# irs-v5.net
KiCad netlist of a schematic drawn in EAGLE
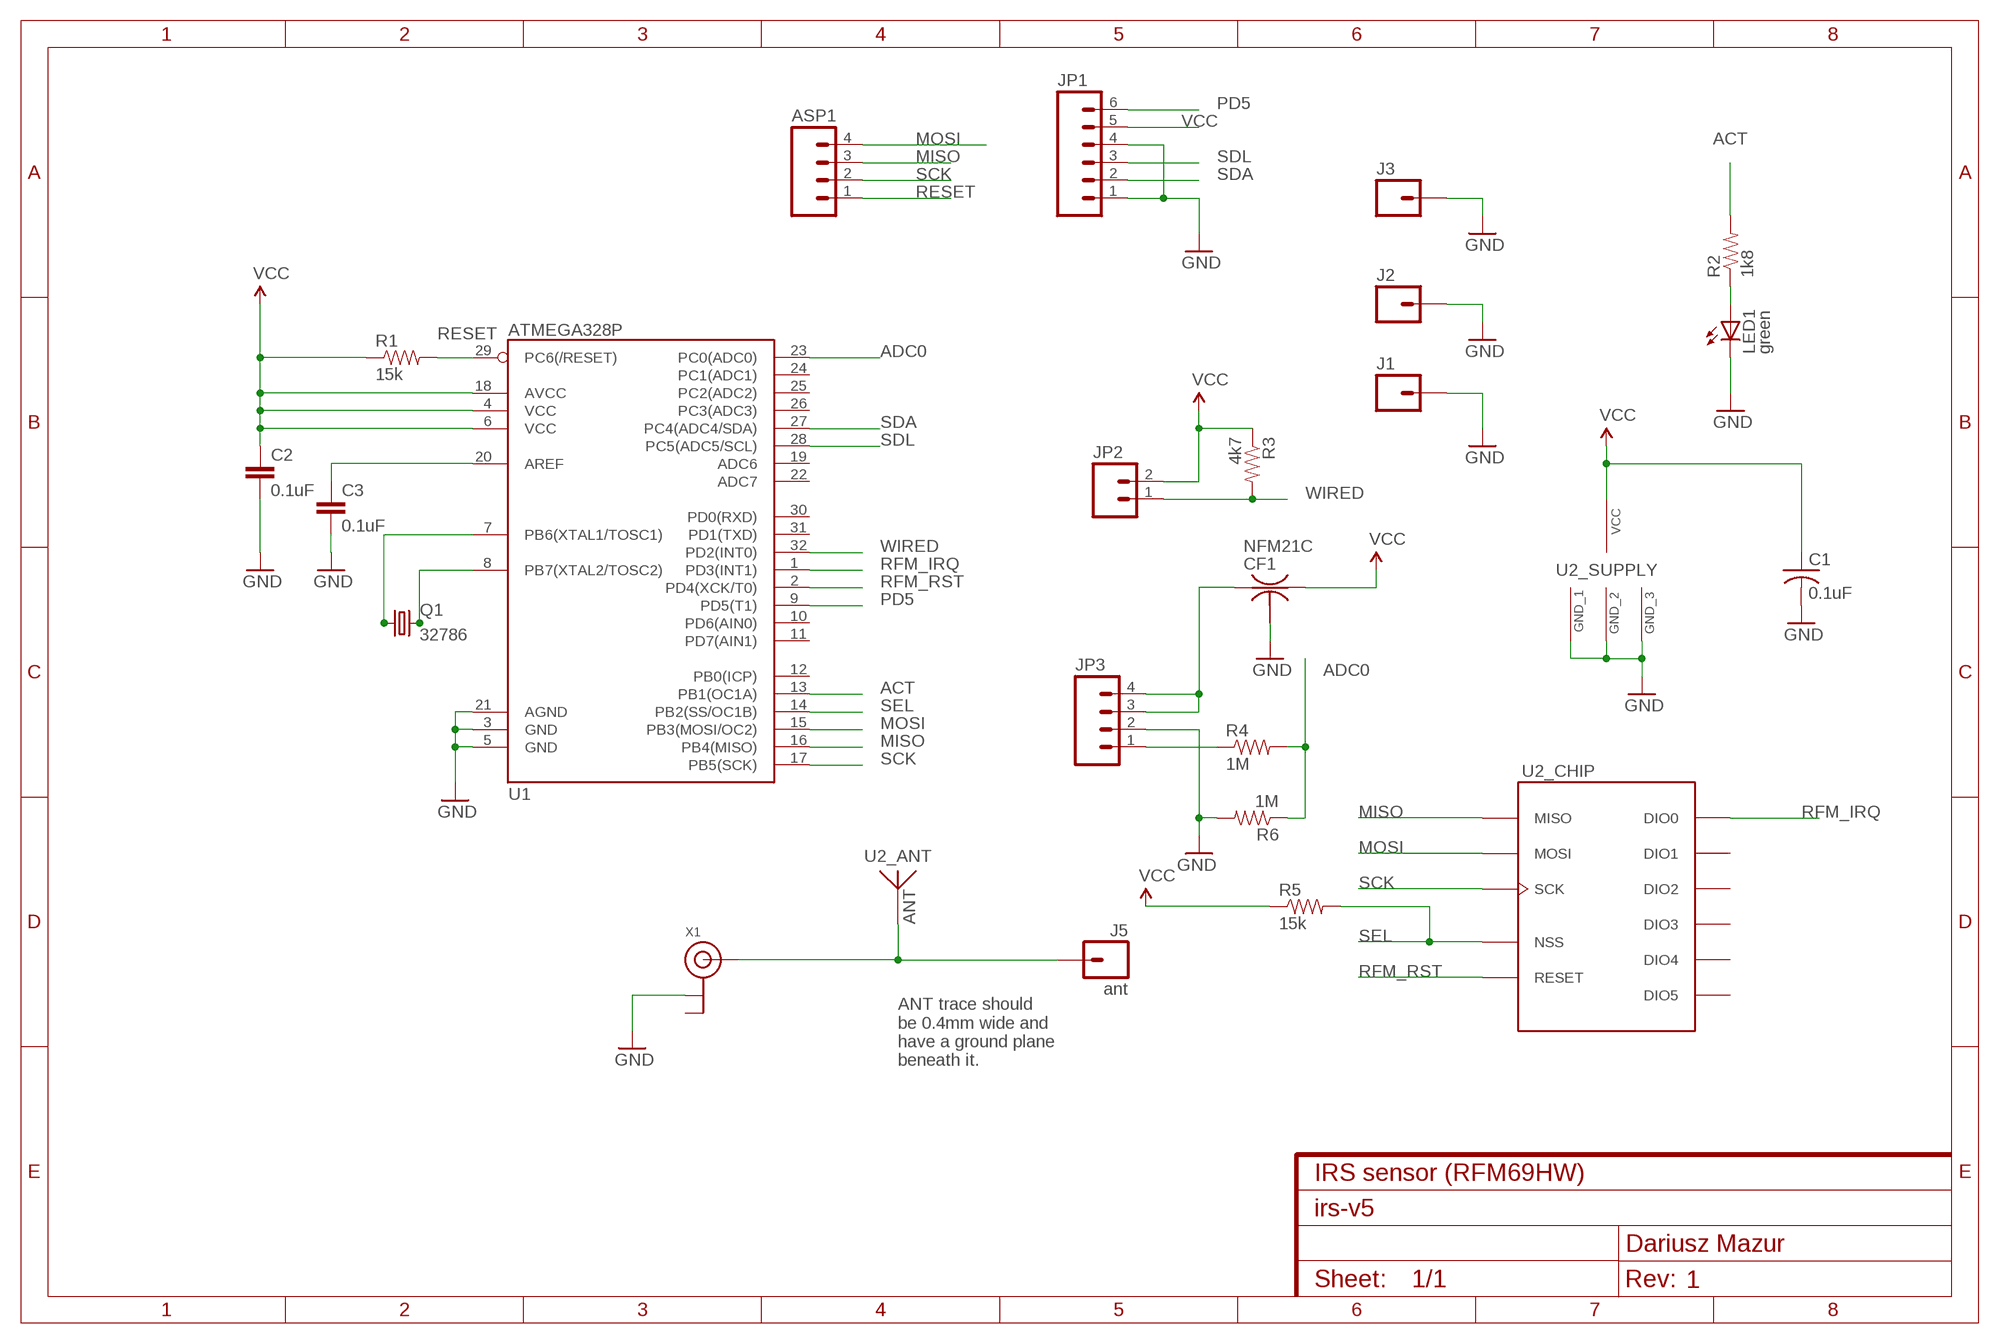
[diagram p0: schematic, sheet 1]

(export (version "E")
  (design (tool "Eeschema 10.0.6"))
  (components
    (comp (ref "ASP1")
      (value "M04NO_SILK_ALL_ROUND")
      (footprint "eagle-import:1X04_NO_SILK_ALL_ROUND")
      (libsource (lib "eagle-import") (part "M04NO_SILK_ALL_ROUND"))
    )
    (comp (ref "C1")
      (value "0.1uF")
      (footprint "eagle-import:C0603")
      (libsource (lib "eagle-import") (part "C-USC0603"))
    )
    (comp (ref "C2")
      (value "0.1uF")
      (footprint "eagle-import:0603-CAP")
      (libsource (lib "eagle-import") (part "0.1UF-25V(+80/-20%)(0603)"))
    )
    (comp (ref "C3")
      (value "0.1uF")
      (footprint "eagle-import:0603-CAP")
      (libsource (lib "eagle-import") (part "0.1UF-25V(+80/-20%)(0603)"))
    )
    (comp (ref "CF1")
      (value "NFM21C")
      (footprint "eagle-import:NFM21C")
      (fields (field (name "MPN") "NFM21CC102R1H3D"))
      (libsource (lib "eagle-import") (part "NFM21C"))
    )
    (comp (ref "J1")
      (value "M01PTH_NO_SILK_YES_STOP")
      (footprint "eagle-import:1X01_NO_SILK")
      (libsource (lib "eagle-import") (part "M01PTH_NO_SILK_YES_STOP"))
    )
    (comp (ref "J2")
      (value "M01PTH_NO_SILK_YES_STOP")
      (footprint "eagle-import:1X01_NO_SILK")
      (libsource (lib "eagle-import") (part "M01PTH_NO_SILK_YES_STOP"))
    )
    (comp (ref "J3")
      (value "M01PTH_NO_SILK_YES_STOP")
      (footprint "eagle-import:1X01_NO_SILK")
      (libsource (lib "eagle-import") (part "M01PTH_NO_SILK_YES_STOP"))
    )
    (comp (ref "J5")
      (value "ant")
      (footprint "eagle-import:1X01_NO_SILK")
      (libsource (lib "eagle-import") (part "M01PTH_NO_SILK_YES_STOP"))
    )
    (comp (ref "JP1")
      (value "M06NO_SILK_FEMALE_PTH")
      (footprint "eagle-import:1X06_NO_SILK")
      (libsource (lib "eagle-import") (part "M06NO_SILK_FEMALE_PTH"))
    )
    (comp (ref "JP2")
      (value "M021X02_NO_SILK")
      (footprint "eagle-import:1X02_NO_SILK")
      (libsource (lib "eagle-import") (part "M021X02_NO_SILK"))
    )
    (comp (ref "JP3")
      (value "M04NO_SILK_ALL_ROUND")
      (footprint "eagle-import:1X04_NO_SILK_ALL_ROUND")
      (libsource (lib "eagle-import") (part "M04NO_SILK_ALL_ROUND"))
    )
    (comp (ref "LED1")
      (value "green")
      (footprint "eagle-import:LED-0603")
      (libsource (lib "eagle-import") (part "LED0603"))
    )
    (comp (ref "Q1")
      (value "32786")
      (footprint "eagle-import:MC-306")
      (fields (field (name "MPN") "MC-306 60.0KHZ  100PPM ,12.5PF"))
      (libsource (lib "eagle-import") (part "MC-306"))
    )
    (comp (ref "R1")
      (value "15k")
      (footprint "eagle-import:0603-RES")
      (libsource (lib "eagle-import") (part "RESISTOR0603-RES"))
    )
    (comp (ref "R2")
      (value "1k8")
      (footprint "eagle-import:0603-RES")
      (libsource (lib "eagle-import") (part "RESISTOR0603-RES"))
    )
    (comp (ref "R3")
      (value "4k7")
      (footprint "eagle-import:0603-RES")
      (libsource (lib "eagle-import") (part "RESISTOR0603-RES"))
    )
    (comp (ref "R4")
      (value "1M")
      (footprint "eagle-import:0603-RES")
      (libsource (lib "eagle-import") (part "RESISTOR0603-RES"))
    )
    (comp (ref "R5")
      (value "15k")
      (footprint "eagle-import:0603-RES")
      (libsource (lib "eagle-import") (part "RESISTOR0603-RES"))
    )
    (comp (ref "R6")
      (value "1M")
      (footprint "eagle-import:0603-RES")
      (libsource (lib "eagle-import") (part "RESISTOR0603-RES"))
    )
    (comp (ref "U1")
      (value "ATMEGA328P")
      (footprint "eagle-import:TQFP32-08")
      (libsource (lib "eagle-import") (part "ATMEGA328_SMT"))
    )
    (comp (ref "U2")
      (value "RFM69HCW-S2")
      (footprint "eagle-import:HOPE-RF-16")
      (libsource (lib "eagle-import") (part "RFM69HCW-S2"))
    )
    (comp (ref "X1")
      (value "ANTENNA_U.FL")
      (footprint "eagle-import:U.FL")
      (libsource (lib "eagle-import") (part "ANTENNA_U.FL"))
    )
  )
  (nets
    (net (code "1") (name "/ACT") (class "Default")
      (node (ref "R2") (pin "2") (pinfunction "2_2") (pintype "passive"))
      (node (ref "U1") (pin "13") (pinfunction "PB1(OC1A)_13") (pintype "bidirectional"))
    )
    (net (code "2") (name "/ADC0") (class "Default")
      (node (ref "R4") (pin "2") (pinfunction "2_2") (pintype "passive"))
      (node (ref "R6") (pin "1") (pinfunction "1_1") (pintype "passive"))
      (node (ref "U1") (pin "23") (pinfunction "PC0(ADC0)_23") (pintype "bidirectional"))
    )
    (net (code "3") (name "/MISO") (class "Default")
      (node (ref "ASP1") (pin "3") (pinfunction "3_3") (pintype "passive"))
      (node (ref "U1") (pin "16") (pinfunction "PB4(MISO)_16") (pintype "bidirectional"))
      (node (ref "U2") (pin "MISO") (pinfunction "MISO_MISO") (pintype "input"))
    )
    (net (code "4") (name "/MOSI") (class "Default")
      (node (ref "ASP1") (pin "4") (pinfunction "4_4") (pintype "passive"))
      (node (ref "U1") (pin "15") (pinfunction "PB3(MOSI/OC2)_15") (pintype "bidirectional"))
      (node (ref "U2") (pin "MOSI") (pinfunction "MOSI_MOSI") (pintype "output"))
    )
    (net (code "5") (name "/PD5") (class "Default")
      (node (ref "JP1") (pin "6") (pinfunction "6_6") (pintype "passive"))
      (node (ref "U1") (pin "9") (pinfunction "PD5(T1)_9") (pintype "bidirectional"))
    )
    (net (code "6") (name "/RESET") (class "Default")
      (node (ref "ASP1") (pin "1") (pinfunction "1_1") (pintype "passive"))
      (node (ref "R1") (pin "2") (pinfunction "2_2") (pintype "passive"))
      (node (ref "U1") (pin "29") (pinfunction "PC6(/RESET)_29") (pintype "bidirectional"))
    )
    (net (code "7") (name "/RFM_IRQ") (class "Default")
      (node (ref "U1") (pin "1") (pinfunction "PD3(INT1)_1") (pintype "bidirectional"))
      (node (ref "U2") (pin "DIO0") (pinfunction "DIO0_DIO0") (pintype "bidirectional"))
    )
    (net (code "8") (name "/RFM_RST") (class "Default")
      (node (ref "U1") (pin "2") (pinfunction "PD4(XCK/T0)_2") (pintype "bidirectional"))
      (node (ref "U2") (pin "RESET") (pinfunction "RESET_RESET") (pintype "bidirectional"))
    )
    (net (code "9") (name "/SCK") (class "Default")
      (node (ref "ASP1") (pin "2") (pinfunction "2_2") (pintype "passive"))
      (node (ref "U1") (pin "17") (pinfunction "PB5(SCK)_17") (pintype "bidirectional"))
      (node (ref "U2") (pin "SCK") (pinfunction "SCK_SCK") (pintype "input"))
    )
    (net (code "10") (name "/SDA") (class "Default")
      (node (ref "JP1") (pin "2") (pinfunction "2_2") (pintype "passive"))
      (node (ref "U1") (pin "27") (pinfunction "PC4(ADC4/SDA)_27") (pintype "bidirectional"))
    )
    (net (code "11") (name "/SDL") (class "Default")
      (node (ref "JP1") (pin "3") (pinfunction "3_3") (pintype "passive"))
      (node (ref "U1") (pin "28") (pinfunction "PC5(ADC5/SCL)_28") (pintype "bidirectional"))
    )
    (net (code "12") (name "/SEL") (class "Default")
      (node (ref "R5") (pin "2") (pinfunction "2_2") (pintype "passive"))
      (node (ref "U1") (pin "14") (pinfunction "PB2(SS/OC1B)_14") (pintype "bidirectional"))
      (node (ref "U2") (pin "NSS") (pinfunction "NSS_NSS") (pintype "input"))
    )
    (net (code "13") (name "/WIRED") (class "Default")
      (node (ref "JP2") (pin "1") (pinfunction "1_1") (pintype "passive"))
      (node (ref "R3") (pin "2") (pinfunction "2_2") (pintype "passive"))
      (node (ref "U1") (pin "32") (pinfunction "PD2(INT0)_32") (pintype "bidirectional"))
    )
    (net (code "14") (name "GND") (class "Default")
      (node (ref "C1") (pin "2") (pinfunction "2_2") (pintype "passive"))
      (node (ref "C2") (pin "2") (pinfunction "2_2") (pintype "passive"))
      (node (ref "C3") (pin "2") (pinfunction "2_2") (pintype "passive"))
      (node (ref "CF1") (pin "2@1") (pinfunction "2_2@1") (pintype "passive"))
      (node (ref "J1") (pin "1") (pinfunction "1_1") (pintype "passive"))
      (node (ref "J2") (pin "1") (pinfunction "1_1") (pintype "passive"))
      (node (ref "J3") (pin "1") (pinfunction "1_1") (pintype "passive"))
      (node (ref "JP1") (pin "1") (pinfunction "1_1") (pintype "passive"))
      (node (ref "JP1") (pin "4") (pinfunction "4_4") (pintype "passive"))
      (node (ref "JP3") (pin "2") (pinfunction "2_2") (pintype "passive"))
      (node (ref "LED1") (pin "C") (pinfunction "C_C") (pintype "passive"))
      (node (ref "R6") (pin "2") (pinfunction "2_2") (pintype "passive"))
      (node (ref "U1") (pin "21") (pinfunction "AGND_21") (pintype "bidirectional"))
      (node (ref "U1") (pin "3") (pinfunction "GND_3") (pintype "bidirectional"))
      (node (ref "U1") (pin "5") (pinfunction "GND_5") (pintype "bidirectional"))
      (node (ref "U2") (pin "GND1") (pinfunction "GND_1_GND1") (pintype "power_in"))
      (node (ref "U2") (pin "GND2") (pinfunction "GND_2_GND2") (pintype "power_in"))
      (node (ref "U2") (pin "GND3") (pinfunction "GND_3_GND3") (pintype "power_in"))
      (node (ref "X1") (pin "1") (pinfunction "GND_1") (pintype "passive"))
    )
    (net (code "15") (name "Net-(CF1-Pad1)") (class "Default")
      (node (ref "CF1") (pin "1") (pinfunction "1_1") (pintype "passive"))
      (node (ref "JP3") (pin "3") (pinfunction "3_3") (pintype "passive"))
      (node (ref "JP3") (pin "4") (pinfunction "4_4") (pintype "passive"))
    )
    (net (code "16") (name "Net-(JP3-Pad1)") (class "Default")
      (node (ref "JP3") (pin "1") (pinfunction "1_1") (pintype "passive"))
      (node (ref "R4") (pin "1") (pinfunction "1_1") (pintype "passive"))
    )
    (net (code "17") (name "Net-(LED1-PadA)") (class "Default")
      (node (ref "LED1") (pin "A") (pinfunction "A_A") (pintype "passive"))
      (node (ref "R2") (pin "1") (pinfunction "1_1") (pintype "passive"))
    )
    (net (code "18") (name "Net-(Q1-2)") (class "Default")
      (node (ref "Q1") (pin "4") (pinfunction "2_4") (pintype "passive"))
      (node (ref "U1") (pin "8") (pinfunction "PB7(XTAL2/TOSC2)_8") (pintype "bidirectional"))
    )
    (net (code "19") (name "Net-(U1-AREF)") (class "Default")
      (node (ref "C3") (pin "1") (pinfunction "1_1") (pintype "passive"))
      (node (ref "U1") (pin "20") (pinfunction "AREF_20") (pintype "bidirectional"))
    )
    (net (code "20") (name "Net-(U1-PB6(XTAL1{slash}TOSC1))") (class "Default")
      (node (ref "Q1") (pin "1") (pinfunction "1_1") (pintype "passive"))
      (node (ref "U1") (pin "7") (pinfunction "PB6(XTAL1/TOSC1)_7") (pintype "bidirectional"))
    )
    (net (code "21") (name "Net-(X1-SIGNAL)") (class "Default")
      (node (ref "J5") (pin "1") (pinfunction "1_1") (pintype "passive"))
      (node (ref "U2") (pin "ANT") (pinfunction "ANT_ANT") (pintype "passive"))
      (node (ref "X1") (pin "3") (pinfunction "SIGNAL_3") (pintype "passive"))
    )
    (net (code "22") (name "VCC") (class "Default")
      (node (ref "C1") (pin "1") (pinfunction "1_1") (pintype "passive"))
      (node (ref "C2") (pin "1") (pinfunction "1_1") (pintype "passive"))
      (node (ref "CF1") (pin "3") (pinfunction "3_3") (pintype "passive"))
      (node (ref "JP1") (pin "5") (pinfunction "5_5") (pintype "passive"))
      (node (ref "JP2") (pin "2") (pinfunction "2_2") (pintype "passive"))
      (node (ref "R1") (pin "1") (pinfunction "1_1") (pintype "passive"))
      (node (ref "R3") (pin "1") (pinfunction "1_1") (pintype "passive"))
      (node (ref "R5") (pin "1") (pinfunction "1_1") (pintype "passive"))
      (node (ref "U1") (pin "18") (pinfunction "AVCC_18") (pintype "bidirectional"))
      (node (ref "U1") (pin "4") (pinfunction "VCC_4") (pintype "bidirectional"))
      (node (ref "U1") (pin "6") (pinfunction "VCC_6") (pintype "bidirectional"))
      (node (ref "U2") (pin "3.3V") (pinfunction "VCC_3.3V") (pintype "power_in"))
    )
    (net (code "23") (name "unconnected-(CF1-2-Pad2@2)") (class "Default")
      (node (ref "CF1") (pin "2@2") (pinfunction "2_2@2") (pintype "passive"))
    )
    (net (code "24") (name "unconnected-(U1-ADC6-Pad19)") (class "Default")
      (node (ref "U1") (pin "19") (pinfunction "ADC6_19") (pintype "bidirectional"))
    )
    (net (code "25") (name "unconnected-(U1-ADC7-Pad22)") (class "Default")
      (node (ref "U1") (pin "22") (pinfunction "ADC7_22") (pintype "bidirectional"))
    )
    (net (code "26") (name "unconnected-(U1-PB0(ICP)-Pad12)") (class "Default")
      (node (ref "U1") (pin "12") (pinfunction "PB0(ICP)_12") (pintype "bidirectional"))
    )
    (net (code "27") (name "unconnected-(U1-PC1(ADC1)-Pad24)") (class "Default")
      (node (ref "U1") (pin "24") (pinfunction "PC1(ADC1)_24") (pintype "bidirectional"))
    )
    (net (code "28") (name "unconnected-(U1-PC2(ADC2)-Pad25)") (class "Default")
      (node (ref "U1") (pin "25") (pinfunction "PC2(ADC2)_25") (pintype "bidirectional"))
    )
    (net (code "29") (name "unconnected-(U1-PC3(ADC3)-Pad26)") (class "Default")
      (node (ref "U1") (pin "26") (pinfunction "PC3(ADC3)_26") (pintype "bidirectional"))
    )
    (net (code "30") (name "unconnected-(U1-PD0(RXD)-Pad30)") (class "Default")
      (node (ref "U1") (pin "30") (pinfunction "PD0(RXD)_30") (pintype "bidirectional"))
    )
    (net (code "31") (name "unconnected-(U1-PD1(TXD)-Pad31)") (class "Default")
      (node (ref "U1") (pin "31") (pinfunction "PD1(TXD)_31") (pintype "bidirectional"))
    )
    (net (code "32") (name "unconnected-(U1-PD6(AIN0)-Pad10)") (class "Default")
      (node (ref "U1") (pin "10") (pinfunction "PD6(AIN0)_10") (pintype "bidirectional"))
    )
    (net (code "33") (name "unconnected-(U1-PD7(AIN1)-Pad11)") (class "Default")
      (node (ref "U1") (pin "11") (pinfunction "PD7(AIN1)_11") (pintype "bidirectional"))
    )
    (net (code "34") (name "unconnected-(U2-PadDIO1)") (class "Default")
      (node (ref "U2") (pin "DIO1") (pinfunction "DIO1_DIO1") (pintype "bidirectional"))
    )
    (net (code "35") (name "unconnected-(U2-PadDIO2)") (class "Default")
      (node (ref "U2") (pin "DIO2") (pinfunction "DIO2_DIO2") (pintype "bidirectional"))
    )
    (net (code "36") (name "unconnected-(U2-PadDIO3)") (class "Default")
      (node (ref "U2") (pin "DIO3") (pinfunction "DIO3_DIO3") (pintype "bidirectional"))
    )
    (net (code "37") (name "unconnected-(U2-PadDIO4)") (class "Default")
      (node (ref "U2") (pin "DIO4") (pinfunction "DIO4_DIO4") (pintype "bidirectional"))
    )
    (net (code "38") (name "unconnected-(U2-PadDIO5)") (class "Default")
      (node (ref "U2") (pin "DIO5") (pinfunction "DIO5_DIO5") (pintype "bidirectional"))
    )
    (net (code "39") (name "unconnected-(X1-GND-Pad2)") (class "Default")
      (node (ref "X1") (pin "2") (pinfunction "GND_2") (pintype "passive"))
    )
  )
)
